# DL-1.net
KiCad netlist of a schematic drawn in EAGLE
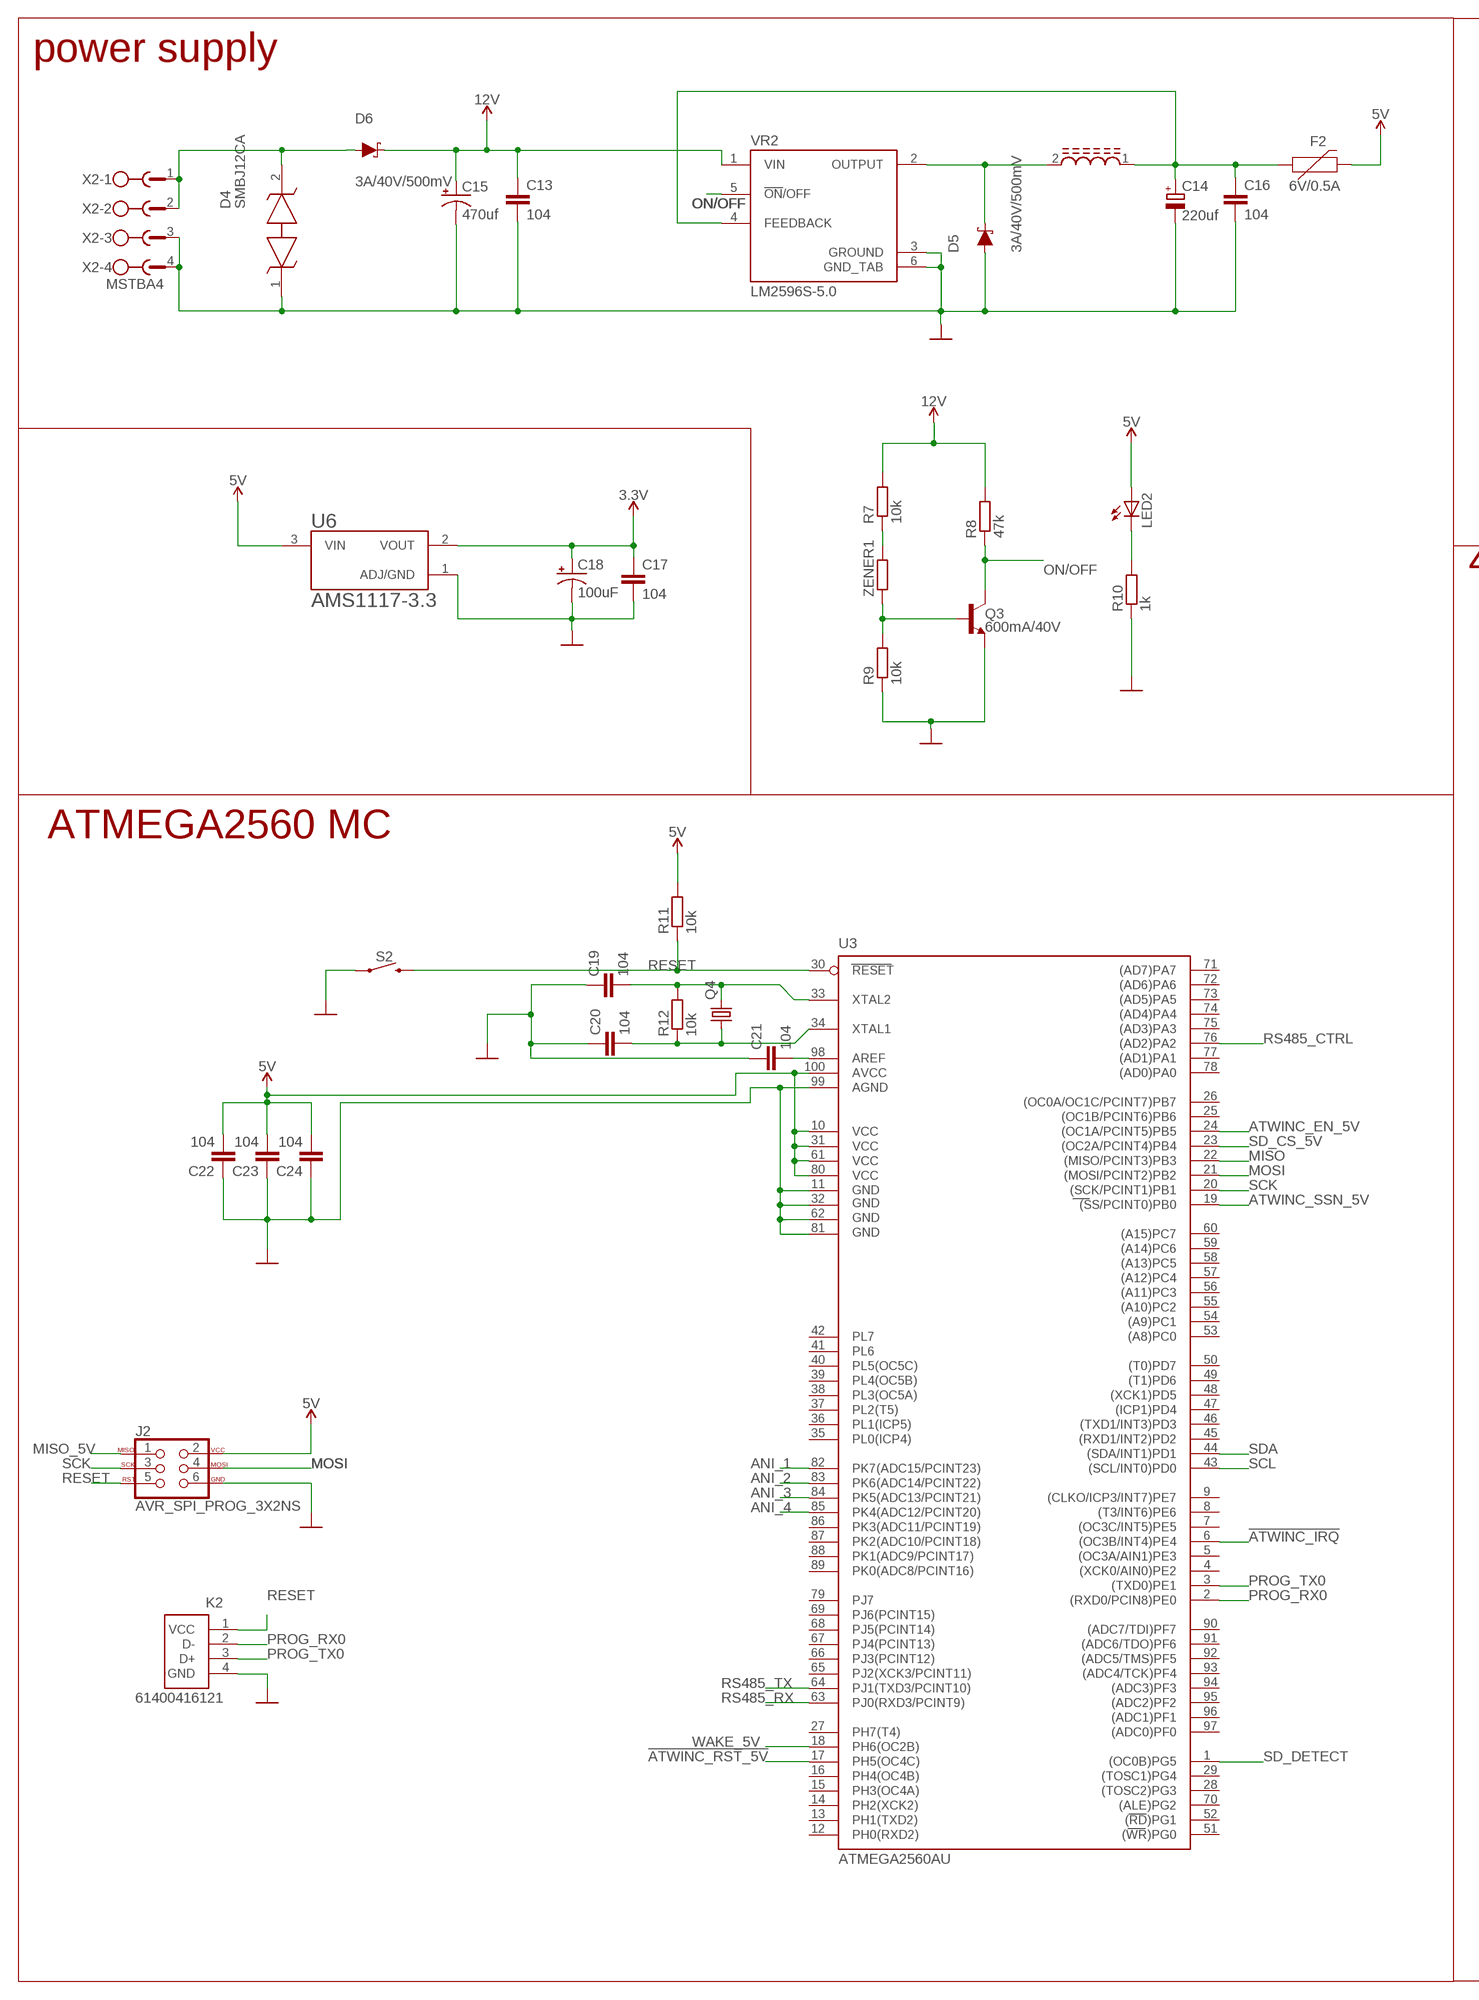
[diagram p0: schematic, sheet 1, part 1 of 2]
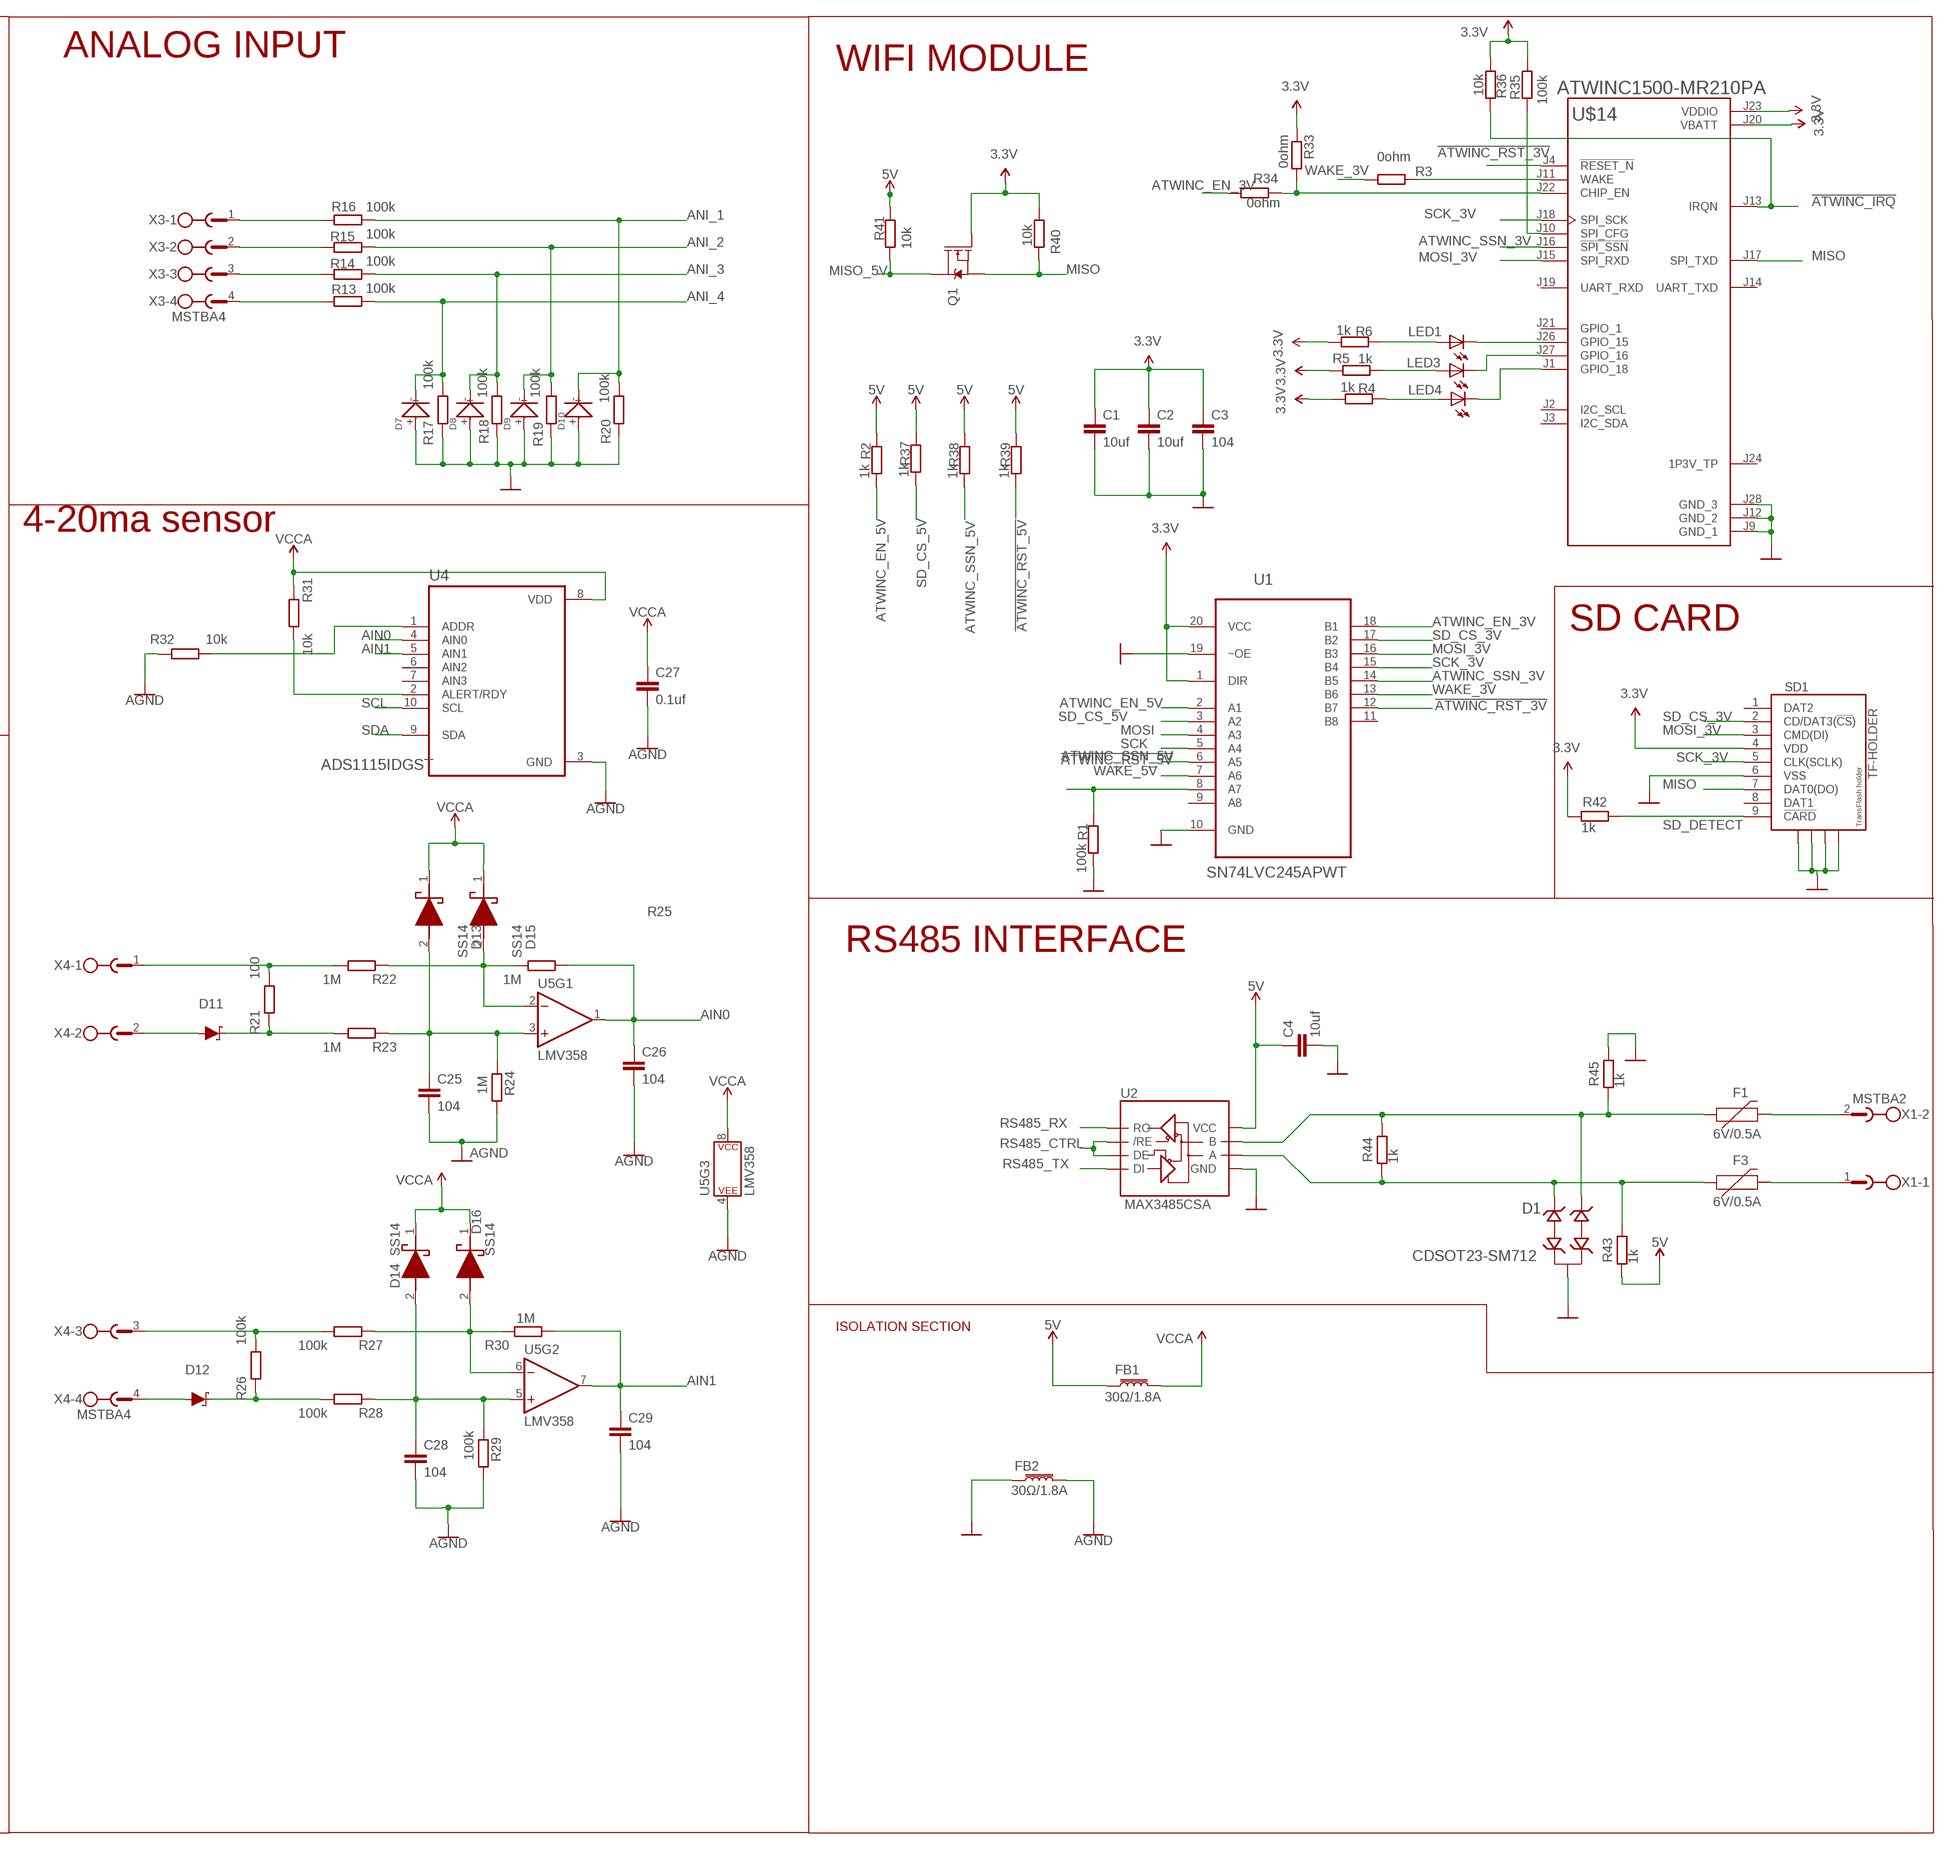
[diagram p1: schematic, sheet 1, part 2 of 2]

(export (version "E")
  (design (tool "Eeschema 10.0.6"))
  (components
    (comp (ref "C1")
      (value "10uf")
      (footprint "eagle-import:C0805")
      (libsource (lib "eagle-import") (part "C-EUC0805"))
    )
    (comp (ref "C2")
      (value "10uf")
      (footprint "eagle-import:C0805")
      (libsource (lib "eagle-import") (part "C-EUC0805"))
    )
    (comp (ref "C3")
      (value "104")
      (footprint "eagle-import:C0805")
      (libsource (lib "eagle-import") (part "C-EUC0805"))
    )
    (comp (ref "C4")
      (value "10uf")
      (footprint "eagle-import:C0805")
      (libsource (lib "eagle-import") (part "C-EUC0805"))
    )
    (comp (ref "C13")
      (value "104")
      (footprint "eagle-import:C0805")
      (libsource (lib "eagle-import") (part "C-EUC0805"))
    )
    (comp (ref "C14")
      (value "220uf")
      (footprint "eagle-import:153CLV-1014")
      (libsource (lib "eagle-import") (part "CPOL-EU153CLV-1014"))
    )
    (comp (ref "C15")
      (value "470uf")
      (footprint "eagle-import:E5-8,5")
      (libsource (lib "eagle-import") (part "CPOL-USE5-8.5"))
    )
    (comp (ref "C16")
      (value "104")
      (footprint "eagle-import:C0805")
      (libsource (lib "eagle-import") (part "C-EUC0805"))
    )
    (comp (ref "C17")
      (value "104")
      (footprint "eagle-import:C0805")
      (libsource (lib "eagle-import") (part "C-EUC0805"))
    )
    (comp (ref "C18")
      (value "100uF")
      (footprint "eagle-import:NIC_10X10.5_CAP")
      (libsource (lib "eagle-import") (part "100UF-POLAR-10X10.5-63V-20%"))
    )
    (comp (ref "C19")
      (value "104")
      (footprint "eagle-import:C0805")
      (libsource (lib "eagle-import") (part "C-EUC0805"))
    )
    (comp (ref "C20")
      (value "104")
      (footprint "eagle-import:C0805")
      (libsource (lib "eagle-import") (part "C-EUC0805"))
    )
    (comp (ref "C21")
      (value "104")
      (footprint "eagle-import:C0805")
      (libsource (lib "eagle-import") (part "C-EUC0805"))
    )
    (comp (ref "C22")
      (value "104")
      (footprint "eagle-import:C0805")
      (libsource (lib "eagle-import") (part "C-EUC0805"))
    )
    (comp (ref "C23")
      (value "104")
      (footprint "eagle-import:C0805")
      (libsource (lib "eagle-import") (part "C-EUC0805"))
    )
    (comp (ref "C24")
      (value "104")
      (footprint "eagle-import:C0805")
      (libsource (lib "eagle-import") (part "C-EUC0805"))
    )
    (comp (ref "C25")
      (value "104")
      (footprint "eagle-import:C0805")
      (libsource (lib "eagle-import") (part "C-EUC0805"))
    )
    (comp (ref "C26")
      (value "104")
      (footprint "eagle-import:C0805")
      (libsource (lib "eagle-import") (part "C-EUC0805"))
    )
    (comp (ref "C27")
      (value "0.1uf")
      (footprint "eagle-import:C0805")
      (libsource (lib "eagle-import") (part "C-EUC0805"))
    )
    (comp (ref "C28")
      (value "104")
      (footprint "eagle-import:C0805")
      (libsource (lib "eagle-import") (part "C-EUC0805"))
    )
    (comp (ref "C29")
      (value "104")
      (footprint "eagle-import:C0805")
      (libsource (lib "eagle-import") (part "C-EUC0805"))
    )
    (comp (ref "D1")
      (value "CDSOT23-SM712")
      (footprint "eagle-import:SOT-23-3")
      (fields (field (name "MF") "Bourns"))
      (libsource (lib "eagle-import") (part "CDSOT23-SM712"))
    )
    (comp (ref "D4")
      (value "SMBJ12CA")
      (footprint "eagle-import:DIONM5443X244N")
      (fields (field (name "MOUSER_PART_NUMBER") "652-SMBJ12CA"))
      (libsource (lib "eagle-import") (part "SMBJ12CA"))
    )
    (comp (ref "D5")
      (value "3A/40V/500mV")
      (footprint "eagle-import:SMA-DIODE")
      (libsource (lib "eagle-import") (part "DIODE-SCHOTTKY-B340A"))
    )
    (comp (ref "D6")
      (value "3A/40V/500mV")
      (footprint "eagle-import:SMA-DIODE")
      (libsource (lib "eagle-import") (part "DIODE-SCHOTTKY-B340A"))
    )
    (comp (ref "D7")
      (value "SMD-DIODE-ZENER-5.1V-500MW(SOD-123)")
      (footprint "eagle-import:SOD-123")
      (fields (field (name "MF") "Vishay") (field (name "MP") "MMSZ4689-V-GS08"))
      (libsource (lib "eagle-import") (part "SMD-DIODE-ZENER-5.1V-500MW(SOD-123)"))
    )
    (comp (ref "D8")
      (value "SMD-DIODE-ZENER-5.1V-500MW(SOD-123)")
      (footprint "eagle-import:SOD-123")
      (fields (field (name "MF") "Vishay") (field (name "MP") "MMSZ4689-V-GS08"))
      (libsource (lib "eagle-import") (part "SMD-DIODE-ZENER-5.1V-500MW(SOD-123)"))
    )
    (comp (ref "D9")
      (value "SMD-DIODE-ZENER-5.1V-500MW(SOD-123)")
      (footprint "eagle-import:SOD-123")
      (fields (field (name "MF") "Vishay") (field (name "MP") "MMSZ4689-V-GS08"))
      (libsource (lib "eagle-import") (part "SMD-DIODE-ZENER-5.1V-500MW(SOD-123)"))
    )
    (comp (ref "D10")
      (value "SMD-DIODE-ZENER-5.1V-500MW(SOD-123)")
      (footprint "eagle-import:SOD-123")
      (fields (field (name "MF") "Vishay") (field (name "MP") "MMSZ4689-V-GS08"))
      (libsource (lib "eagle-import") (part "SMD-DIODE-ZENER-5.1V-500MW(SOD-123)"))
    )
    (comp (ref "D11")
      (value "3A/40V/500mV")
      (footprint "eagle-import:SMA-DIODE")
      (libsource (lib "eagle-import") (part "DIODE-SCHOTTKY-B340A"))
    )
    (comp (ref "D12")
      (value "3A/40V/500mV")
      (footprint "eagle-import:SMA-DIODE")
      (libsource (lib "eagle-import") (part "DIODE-SCHOTTKY-B340A"))
    )
    (comp (ref "D13")
      (value "SS14")
      (footprint "eagle-import:DIOM5227X270N")
      (fields (field (name "MOUSER_PART_NUMBER") "512-SS14"))
      (libsource (lib "eagle-import") (part "SS14"))
    )
    (comp (ref "D14")
      (value "SS14")
      (footprint "eagle-import:DIOM5227X270N")
      (fields (field (name "MOUSER_PART_NUMBER") "512-SS14"))
      (libsource (lib "eagle-import") (part "SS14"))
    )
    (comp (ref "D15")
      (value "SS14")
      (footprint "eagle-import:DIOM5227X270N")
      (fields (field (name "MOUSER_PART_NUMBER") "512-SS14"))
      (libsource (lib "eagle-import") (part "SS14"))
    )
    (comp (ref "D16")
      (value "SS14")
      (footprint "eagle-import:DIOM5227X270N")
      (fields (field (name "MOUSER_PART_NUMBER") "512-SS14"))
      (libsource (lib "eagle-import") (part "SS14"))
    )
    (comp (ref "F1")
      (value "6V/0.5A")
      (footprint "eagle-import:1206")
      (libsource (lib "eagle-import") (part "PPTC_HALF-AMP"))
    )
    (comp (ref "F2")
      (value "6V/0.5A")
      (footprint "eagle-import:1206")
      (libsource (lib "eagle-import") (part "PPTC_HALF-AMP"))
    )
    (comp (ref "F3")
      (value "6V/0.5A")
      (footprint "eagle-import:1206")
      (libsource (lib "eagle-import") (part "PPTC_HALF-AMP"))
    )
    (comp (ref "FB1")
      (value "30Ω/1.8A")
      (footprint "eagle-import:0603")
      (libsource (lib "eagle-import") (part "FERRITE_BEAD-0603"))
    )
    (comp (ref "FB2")
      (value "30Ω/1.8A")
      (footprint "eagle-import:0603")
      (libsource (lib "eagle-import") (part "FERRITE_BEAD-0603"))
    )
    (comp (ref "J2")
      (value "AVR_SPI_PROG_3X2NS")
      (footprint "eagle-import:2X3-NS")
      (libsource (lib "eagle-import") (part "AVR_SPI_PROG_3X2NS"))
    )
    (comp (ref "K2")
      (value "61400416121")
      (footprint "eagle-import:61400416121")
      (libsource (lib "eagle-import") (part "61400416121"))
    )
    (comp (ref "L2")
      (value "SRR1260-680M")
      (footprint "eagle-import:INDP125125X600N")
      (fields (field (name "MF") "Bourns"))
      (libsource (lib "eagle-import") (part "SRR1260-680M"))
    )
    (comp (ref "LED1")
      (value "LEDCHIP-LED0805")
      (footprint "eagle-import:CHIP-LED0805")
      (libsource (lib "eagle-import") (part "LEDCHIP-LED0805"))
    )
    (comp (ref "LED2")
      (value "LEDCHIP-LED0805")
      (footprint "eagle-import:CHIP-LED0805")
      (libsource (lib "eagle-import") (part "LEDCHIP-LED0805"))
    )
    (comp (ref "LED3")
      (value "LEDCHIP-LED0805")
      (footprint "eagle-import:CHIP-LED0805")
      (libsource (lib "eagle-import") (part "LEDCHIP-LED0805"))
    )
    (comp (ref "LED4")
      (value "LEDCHIP-LED0805")
      (footprint "eagle-import:CHIP-LED0805")
      (libsource (lib "eagle-import") (part "LEDCHIP-LED0805"))
    )
    (comp (ref "Q1")
      (value "220mA/50V/3.5Ω")
      (footprint "eagle-import:SOT23-3")
      (libsource (lib "eagle-import") (part "MOSFET-NCH-BSS138"))
    )
    (comp (ref "Q3")
      (value "600mA/40V")
      (footprint "eagle-import:SOT23-3")
      (libsource (lib "eagle-import") (part "TRANS_NPN-MMBT2222AL"))
    )
    (comp (ref "Q4")
      (value "CRYSTALHC49S")
      (footprint "eagle-import:HC49_S")
      (libsource (lib "eagle-import") (part "CRYSTALHC49S"))
    )
    (comp (ref "R1")
      (value "100k")
      (footprint "eagle-import:M0805")
      (libsource (lib "eagle-import") (part "R-EU_M0805"))
    )
    (comp (ref "R2")
      (value "1k")
      (footprint "eagle-import:M0805")
      (libsource (lib "eagle-import") (part "R-EU_M0805"))
    )
    (comp (ref "R3")
      (value "0ohm")
      (footprint "eagle-import:M0805")
      (libsource (lib "eagle-import") (part "R-EU_M0805"))
    )
    (comp (ref "R4")
      (value "1k")
      (footprint "eagle-import:M0805")
      (libsource (lib "eagle-import") (part "R-EU_M0805"))
    )
    (comp (ref "R5")
      (value "1k")
      (footprint "eagle-import:M0805")
      (libsource (lib "eagle-import") (part "R-EU_M0805"))
    )
    (comp (ref "R6")
      (value "1k")
      (footprint "eagle-import:M0805")
      (libsource (lib "eagle-import") (part "R-EU_M0805"))
    )
    (comp (ref "R7")
      (value "10k")
      (footprint "eagle-import:M0805")
      (libsource (lib "eagle-import") (part "R-EU_M0805"))
    )
    (comp (ref "R8")
      (value "47k")
      (footprint "eagle-import:M0805")
      (libsource (lib "eagle-import") (part "R-EU_M0805"))
    )
    (comp (ref "R9")
      (value "10k")
      (footprint "eagle-import:M0805")
      (libsource (lib "eagle-import") (part "R-EU_M0805"))
    )
    (comp (ref "R10")
      (value "1k")
      (footprint "eagle-import:M0805")
      (libsource (lib "eagle-import") (part "R-EU_M0805"))
    )
    (comp (ref "R11")
      (value "10k")
      (footprint "eagle-import:M0805")
      (libsource (lib "eagle-import") (part "R-EU_M0805"))
    )
    (comp (ref "R12")
      (value "10k")
      (footprint "eagle-import:M0805")
      (libsource (lib "eagle-import") (part "R-EU_M0805"))
    )
    (comp (ref "R13")
      (value "100k")
      (footprint "eagle-import:M0805")
      (libsource (lib "eagle-import") (part "R-EU_M0805"))
    )
    (comp (ref "R14")
      (value "100k")
      (footprint "eagle-import:M0805")
      (libsource (lib "eagle-import") (part "R-EU_M0805"))
    )
    (comp (ref "R15")
      (value "100k")
      (footprint "eagle-import:M0805")
      (libsource (lib "eagle-import") (part "R-EU_M0805"))
    )
    (comp (ref "R16")
      (value "100k")
      (footprint "eagle-import:M0805")
      (libsource (lib "eagle-import") (part "R-EU_M0805"))
    )
    (comp (ref "R17")
      (value "100k")
      (footprint "eagle-import:M0805")
      (libsource (lib "eagle-import") (part "R-EU_M0805"))
    )
    (comp (ref "R18")
      (value "100k")
      (footprint "eagle-import:M0805")
      (libsource (lib "eagle-import") (part "R-EU_M0805"))
    )
    (comp (ref "R19")
      (value "100k")
      (footprint "eagle-import:M0805")
      (libsource (lib "eagle-import") (part "R-EU_M0805"))
    )
    (comp (ref "R20")
      (value "100k")
      (footprint "eagle-import:M0805")
      (libsource (lib "eagle-import") (part "R-EU_M0805"))
    )
    (comp (ref "R21")
      (value "100")
      (footprint "eagle-import:M0805")
      (libsource (lib "eagle-import") (part "R-EU_M0805"))
    )
    (comp (ref "R22")
      (value "1M")
      (footprint "eagle-import:M0805")
      (libsource (lib "eagle-import") (part "R-EU_M0805"))
    )
    (comp (ref "R23")
      (value "1M")
      (footprint "eagle-import:M0805")
      (libsource (lib "eagle-import") (part "R-EU_M0805"))
    )
    (comp (ref "R24")
      (value "1M")
      (footprint "eagle-import:M0805")
      (libsource (lib "eagle-import") (part "R-EU_M0805"))
    )
    (comp (ref "R25")
      (value "1M")
      (footprint "eagle-import:M0805")
      (libsource (lib "eagle-import") (part "R-EU_M0805"))
    )
    (comp (ref "R26")
      (value "100k")
      (footprint "eagle-import:M0805")
      (libsource (lib "eagle-import") (part "R-EU_M0805"))
    )
    (comp (ref "R27")
      (value "100k")
      (footprint "eagle-import:M0805")
      (libsource (lib "eagle-import") (part "R-EU_M0805"))
    )
    (comp (ref "R28")
      (value "100k")
      (footprint "eagle-import:M0805")
      (libsource (lib "eagle-import") (part "R-EU_M0805"))
    )
    (comp (ref "R29")
      (value "100k")
      (footprint "eagle-import:M0805")
      (libsource (lib "eagle-import") (part "R-EU_M0805"))
    )
    (comp (ref "R30")
      (value "1M")
      (footprint "eagle-import:M0805")
      (libsource (lib "eagle-import") (part "R-EU_M0805"))
    )
    (comp (ref "R31")
      (value "10k")
      (footprint "eagle-import:M0805")
      (libsource (lib "eagle-import") (part "R-EU_M0805"))
    )
    (comp (ref "R32")
      (value "10k")
      (footprint "eagle-import:M0805")
      (libsource (lib "eagle-import") (part "R-EU_M0805"))
    )
    (comp (ref "R33")
      (value "0ohm")
      (footprint "eagle-import:M0805")
      (libsource (lib "eagle-import") (part "R-EU_M0805"))
    )
    (comp (ref "R34")
      (value "0ohm")
      (footprint "eagle-import:M0805")
      (libsource (lib "eagle-import") (part "R-EU_M0805"))
    )
    (comp (ref "R35")
      (value "100k")
      (footprint "eagle-import:M0805")
      (libsource (lib "eagle-import") (part "R-EU_M0805"))
    )
    (comp (ref "R36")
      (value "10k")
      (footprint "eagle-import:M0805")
      (libsource (lib "eagle-import") (part "R-EU_M0805"))
    )
    (comp (ref "R37")
      (value "1k")
      (footprint "eagle-import:M0805")
      (libsource (lib "eagle-import") (part "R-EU_M0805"))
    )
    (comp (ref "R38")
      (value "1k")
      (footprint "eagle-import:M0805")
      (libsource (lib "eagle-import") (part "R-EU_M0805"))
    )
    (comp (ref "R39")
      (value "1k")
      (footprint "eagle-import:M0805")
      (libsource (lib "eagle-import") (part "R-EU_M0805"))
    )
    (comp (ref "R40")
      (value "10k")
      (footprint "eagle-import:M0805")
      (libsource (lib "eagle-import") (part "R-EU_M0805"))
    )
    (comp (ref "R41")
      (value "10k")
      (footprint "eagle-import:M0805")
      (libsource (lib "eagle-import") (part "R-EU_M0805"))
    )
    (comp (ref "R42")
      (value "1k")
      (footprint "eagle-import:M0805")
      (libsource (lib "eagle-import") (part "R-EU_M0805"))
    )
    (comp (ref "R43")
      (value "1k")
      (footprint "eagle-import:M0805")
      (libsource (lib "eagle-import") (part "R-EU_M0805"))
    )
    (comp (ref "R44")
      (value "1k")
      (footprint "eagle-import:M0805")
      (libsource (lib "eagle-import") (part "R-EU_M0805"))
    )
    (comp (ref "R45")
      (value "1k")
      (footprint "eagle-import:M0805")
      (libsource (lib "eagle-import") (part "R-EU_M0805"))
    )
    (comp (ref "S2")
      (value "MOMENTARY-SWITCH-SPST-SMD-6.0X3.5MM")
      (footprint "eagle-import:TACTILE_SWITCH_SMD_6.0X3.5MM")
      (libsource (lib "eagle-import") (part "MOMENTARY-SWITCH-SPST-SMD-6.0X3.5MM"))
    )
    (comp (ref "SD1")
      (value "TF-HOLDER")
      (footprint "eagle-import:TF-PULL")
      (libsource (lib "eagle-import") (part "TF-HOLDER"))
    )
    (comp (ref "U$14")
      (value "ATWINC1500-MR210PA")
      (footprint "eagle-import:ATMEL_ATWINC1500-MR210PA")
      (fields (field (name "MF") "Microchip"))
      (libsource (lib "eagle-import") (part "ATWINC1500-MR210PA"))
    )
    (comp (ref "U1")
      (value "SN74LVC245APWT")
      (footprint "eagle-import:SOP65P640X120-20N")
      (fields (field (name "MF") "Texas Instruments"))
      (libsource (lib "eagle-import") (part "SN74LVC245APWT"))
    )
    (comp (ref "U2")
      (value "MAX3485CSA")
      (footprint "eagle-import:SO08")
      (libsource (lib "eagle-import") (part "RS485SOIC"))
    )
    (comp (ref "U3")
      (value "ATMEGA2560AU")
      (footprint "eagle-import:TQFP100")
      (libsource (lib "eagle-import") (part "ATMEGA2560AU"))
    )
    (comp (ref "U4")
      (value "ADS1115IDGST")
      (footprint "eagle-import:SOP50P490X110-10N")
      (fields (field (name "MF") "Texas Instruments"))
      (libsource (lib "eagle-import") (part "ADS1115IDGST"))
    )
    (comp (ref "U5")
      (value "LMV358")
      (footprint "eagle-import:SO08")
      (libsource (lib "eagle-import") (part "LMV358SOIC"))
    )
    (comp (ref "U6")
      (value "AMS1117-3.3")
      (footprint "eagle-import:SOT229P700X180-4N")
      (fields (field (name "MF") "Advanced Monolithic Systems"))
      (libsource (lib "eagle-import") (part "AMS1117-3.3"))
    )
    (comp (ref "VR2")
      (value "LM2596S-5.0")
      (footprint "eagle-import:TO170P1524X483-6N")
      (fields (field (name "MF") "Texas"))
      (libsource (lib "eagle-import") (part "LM2596S-5.0"))
    )
    (comp (ref "X1")
      (value "MSTBA2")
      (footprint "eagle-import:MSTBA2")
      (fields (field (name "MF") "FARNELL") (field (name "MPN") "1757242"))
      (libsource (lib "eagle-import") (part "MSTBA2"))
    )
    (comp (ref "X2")
      (value "MSTBA4")
      (footprint "eagle-import:MSTBA4")
      (fields (field (name "MF") "FARNELL") (field (name "MPN") "1757268"))
      (libsource (lib "eagle-import") (part "MSTBA4"))
    )
    (comp (ref "X3")
      (value "MSTBA4")
      (footprint "eagle-import:MSTBA4")
      (fields (field (name "MF") "FARNELL") (field (name "MPN") "1757268"))
      (libsource (lib "eagle-import") (part "MSTBA4"))
    )
    (comp (ref "X4")
      (value "MSTBA4")
      (footprint "eagle-import:MSTBA4")
      (fields (field (name "MF") "FARNELL") (field (name "MPN") "1757268"))
      (libsource (lib "eagle-import") (part "MSTBA4"))
    )
    (comp (ref "ZENER1")
      (value "R-EU_0204/7")
      (footprint "eagle-import:0204_7")
      (libsource (lib "eagle-import") (part "R-EU_0204/7"))
    )
  )
  (nets
    (net (code "1") (name "/AIN0") (class "Default")
      (node (ref "C26") (pin "1") (pinfunction "1_1") (pintype "passive"))
      (node (ref "R25") (pin "1") (pinfunction "1_1") (pintype "passive"))
      (node (ref "U4") (pin "4") (pinfunction "AIN0_4") (pintype "input"))
      (node (ref "U5") (pin "1") (pinfunction "OUT_1") (pintype "output"))
    )
    (net (code "2") (name "/AIN1") (class "Default")
      (node (ref "C29") (pin "1") (pinfunction "1_1") (pintype "passive"))
      (node (ref "R30") (pin "1") (pinfunction "1_1") (pintype "passive"))
      (node (ref "U4") (pin "5") (pinfunction "AIN1_5") (pintype "input"))
      (node (ref "U5") (pin "7") (pinfunction "OUT_7") (pintype "output"))
    )
    (net (code "3") (name "/ANI_1") (class "Default")
      (node (ref "D10") (pin "-") (pinfunction "-_-") (pintype "passive"))
      (node (ref "R16") (pin "1") (pinfunction "1_1") (pintype "passive"))
      (node (ref "R20") (pin "2") (pinfunction "2_2") (pintype "passive"))
      (node (ref "U3") (pin "82") (pinfunction "PK7(ADC15/PCINT23)_82") (pintype "bidirectional"))
    )
    (net (code "4") (name "/ANI_2") (class "Default")
      (node (ref "D9") (pin "-") (pinfunction "-_-") (pintype "passive"))
      (node (ref "R15") (pin "1") (pinfunction "1_1") (pintype "passive"))
      (node (ref "R19") (pin "2") (pinfunction "2_2") (pintype "passive"))
      (node (ref "U3") (pin "83") (pinfunction "PK6(ADC14/PCINT22)_83") (pintype "bidirectional"))
    )
    (net (code "5") (name "/ANI_3") (class "Default")
      (node (ref "D8") (pin "-") (pinfunction "-_-") (pintype "passive"))
      (node (ref "R14") (pin "1") (pinfunction "1_1") (pintype "passive"))
      (node (ref "R18") (pin "2") (pinfunction "2_2") (pintype "passive"))
      (node (ref "U3") (pin "84") (pinfunction "PK5(ADC13/PCINT21)_84") (pintype "bidirectional"))
    )
    (net (code "6") (name "/ANI_4") (class "Default")
      (node (ref "D7") (pin "-") (pinfunction "-_-") (pintype "passive"))
      (node (ref "R13") (pin "1") (pinfunction "1_1") (pintype "passive"))
      (node (ref "R17") (pin "2") (pinfunction "2_2") (pintype "passive"))
      (node (ref "U3") (pin "85") (pinfunction "PK4(ADC12/PCINT20)_85") (pintype "bidirectional"))
    )
    (net (code "7") (name "/ATWINC_EN_3V") (class "Default")
      (node (ref "R34") (pin "1") (pinfunction "1_1") (pintype "passive"))
      (node (ref "U1") (pin "18") (pinfunction "B1_18") (pintype "bidirectional"))
    )
    (net (code "8") (name "/ATWINC_EN_5V") (class "Default")
      (node (ref "R2") (pin "2") (pinfunction "2_2") (pintype "passive"))
      (node (ref "U1") (pin "2") (pinfunction "A1_2") (pintype "bidirectional"))
      (node (ref "U3") (pin "24") (pinfunction "(OC1A/PCINT5)PB5_24") (pintype "bidirectional"))
    )
    (net (code "9") (name "/ATWINC_SSN_3V") (class "Default")
      (node (ref "U$14") (pin "J16") (pinfunction "~{SPI_SSN}_J16") (pintype "input"))
      (node (ref "U1") (pin "14") (pinfunction "B5_14") (pintype "bidirectional"))
    )
    (net (code "10") (name "/ATWINC_SSN_5V") (class "Default")
      (node (ref "R38") (pin "2") (pinfunction "2_2") (pintype "passive"))
      (node (ref "U1") (pin "6") (pinfunction "A5_6") (pintype "bidirectional"))
      (node (ref "U3") (pin "19") (pinfunction "(SS/PCINT0)PB0_19") (pintype "bidirectional"))
    )
    (net (code "11") (name "/MISO") (class "Default")
      (node (ref "Q1") (pin "2") (pinfunction "S_2") (pintype "bidirectional"))
      (node (ref "R40") (pin "2") (pinfunction "2_2") (pintype "passive"))
      (node (ref "SD1") (pin "7") (pinfunction "DAT0(DO)_7") (pintype "bidirectional"))
      (node (ref "U$14") (pin "J17") (pinfunction "SPI_TXD_J17") (pintype "output"))
      (node (ref "U3") (pin "22") (pinfunction "(MISO/PCINT3)PB3_22") (pintype "bidirectional"))
    )
    (net (code "12") (name "/MISO_5V") (class "Default")
      (node (ref "J2") (pin "1") (pinfunction "1_1") (pintype "passive"))
      (node (ref "Q1") (pin "3") (pinfunction "D_3") (pintype "bidirectional"))
      (node (ref "R41") (pin "2") (pinfunction "2_2") (pintype "passive"))
    )
    (net (code "13") (name "/MOSI") (class "Default")
      (node (ref "J2") (pin "4") (pinfunction "4_4") (pintype "passive"))
      (node (ref "U1") (pin "4") (pinfunction "A3_4") (pintype "bidirectional"))
      (node (ref "U3") (pin "21") (pinfunction "(MOSI/PCINT2)PB2_21") (pintype "bidirectional"))
    )
    (net (code "14") (name "/MOSI_3V") (class "Default")
      (node (ref "SD1") (pin "3") (pinfunction "CMD(DI)_3") (pintype "bidirectional"))
      (node (ref "U$14") (pin "J15") (pinfunction "SPI_RXD_J15") (pintype "input"))
      (node (ref "U1") (pin "16") (pinfunction "B3_16") (pintype "bidirectional"))
    )
    (net (code "15") (name "/ON{slash}OFF") (class "Default")
      (node (ref "Q3") (pin "3") (pinfunction "C_3") (pintype "passive"))
      (node (ref "R8") (pin "1") (pinfunction "1_1") (pintype "passive"))
      (node (ref "VR2") (pin "5") (pinfunction "~{ON}/OFF_5") (pintype "input"))
    )
    (net (code "16") (name "/PROG_RX0") (class "Default")
      (node (ref "K2") (pin "2") (pinfunction "D-_2") (pintype "passive"))
      (node (ref "U3") (pin "2") (pinfunction "(RXD0/PCIN8)PE0_2") (pintype "bidirectional"))
    )
    (net (code "17") (name "/PROG_TX0") (class "Default")
      (node (ref "K2") (pin "3") (pinfunction "D+_3") (pintype "passive"))
      (node (ref "U3") (pin "3") (pinfunction "(TXD0)PE1_3") (pintype "bidirectional"))
    )
    (net (code "18") (name "/RESET") (class "Default")
      (node (ref "J2") (pin "5") (pinfunction "5_5") (pintype "passive"))
      (node (ref "K2") (pin "1") (pinfunction "VCC_1") (pintype "passive"))
      (node (ref "R11") (pin "1") (pinfunction "1_1") (pintype "passive"))
      (node (ref "S2") (pin "2") (pinfunction "2_2") (pintype "passive"))
      (node (ref "U3") (pin "30") (pinfunction "RESET_30") (pintype "input"))
    )
    (net (code "19") (name "/RS485_CTRL") (class "Default")
      (node (ref "U2") (pin "2") (pinfunction "/RE_2") (pintype "bidirectional"))
      (node (ref "U2") (pin "3") (pinfunction "DE_3") (pintype "bidirectional"))
      (node (ref "U3") (pin "76") (pinfunction "(AD2)PA2_76") (pintype "bidirectional"))
    )
    (net (code "20") (name "/RS485_RX") (class "Default")
      (node (ref "U2") (pin "1") (pinfunction "RO_1") (pintype "bidirectional"))
      (node (ref "U3") (pin "63") (pinfunction "PJ0(RXD3/PCINT9)_63") (pintype "bidirectional"))
    )
    (net (code "21") (name "/RS485_TX") (class "Default")
      (node (ref "U2") (pin "4") (pinfunction "DI_4") (pintype "bidirectional"))
      (node (ref "U3") (pin "64") (pinfunction "PJ1(TXD3/PCINT10)_64") (pintype "bidirectional"))
    )
    (net (code "22") (name "/SCK") (class "Default")
      (node (ref "J2") (pin "3") (pinfunction "3_3") (pintype "passive"))
      (node (ref "U1") (pin "5") (pinfunction "A4_5") (pintype "bidirectional"))
      (node (ref "U3") (pin "20") (pinfunction "(SCK/PCINT1)PB1_20") (pintype "bidirectional"))
    )
    (net (code "23") (name "/SCK_3V") (class "Default")
      (node (ref "SD1") (pin "5") (pinfunction "CLK(SCLK)_5") (pintype "input"))
      (node (ref "U$14") (pin "J18") (pinfunction "SPI_SCK_J18") (pintype "input"))
      (node (ref "U1") (pin "15") (pinfunction "B4_15") (pintype "bidirectional"))
    )
    (net (code "24") (name "/SCL") (class "Default")
      (node (ref "U3") (pin "43") (pinfunction "(SCL/INT0)PD0_43") (pintype "bidirectional"))
      (node (ref "U4") (pin "10") (pinfunction "SCL_10") (pintype "input"))
    )
    (net (code "25") (name "/SDA") (class "Default")
      (node (ref "U3") (pin "44") (pinfunction "(SDA/INT1)PD1_44") (pintype "bidirectional"))
      (node (ref "U4") (pin "9") (pinfunction "SDA_9") (pintype "bidirectional"))
    )
    (net (code "26") (name "/SD_CS_3V") (class "Default")
      (node (ref "SD1") (pin "2") (pinfunction "CD/DAT3(~{CS})_2") (pintype "bidirectional"))
      (node (ref "U1") (pin "17") (pinfunction "B2_17") (pintype "bidirectional"))
    )
    (net (code "27") (name "/SD_CS_5V") (class "Default")
      (node (ref "R37") (pin "2") (pinfunction "2_2") (pintype "passive"))
      (node (ref "U1") (pin "3") (pinfunction "A2_3") (pintype "bidirectional"))
      (node (ref "U3") (pin "23") (pinfunction "(OC2A/PCINT4)PB4_23") (pintype "bidirectional"))
    )
    (net (code "28") (name "/SD_DETECT") (class "Default")
      (node (ref "R42") (pin "2") (pinfunction "2_2") (pintype "passive"))
      (node (ref "SD1") (pin "9") (pinfunction "~{CARD}_9") (pintype "passive"))
      (node (ref "U3") (pin "1") (pinfunction "(OC0B)PG5_1") (pintype "bidirectional"))
    )
    (net (code "29") (name "/WAKE_3V") (class "Default")
      (node (ref "R3") (pin "2") (pinfunction "2_2") (pintype "passive"))
      (node (ref "U1") (pin "13") (pinfunction "B6_13") (pintype "bidirectional"))
    )
    (net (code "30") (name "/WAKE_5V") (class "Default")
      (node (ref "U1") (pin "7") (pinfunction "A6_7") (pintype "bidirectional"))
      (node (ref "U3") (pin "18") (pinfunction "PH6(OC2B)_18") (pintype "bidirectional"))
    )
    (net (code "31") (name "/~{ATWINC_IRQ}") (class "Default")
      (node (ref "R36") (pin "2") (pinfunction "2_2") (pintype "passive"))
      (node (ref "U$14") (pin "J13") (pinfunction "IRQN_J13") (pintype "output"))
      (node (ref "U3") (pin "6") (pinfunction "(OC3B/INT4)PE4_6") (pintype "bidirectional"))
    )
    (net (code "32") (name "/~{ATWINC_RST_3V}") (class "Default")
      (node (ref "U$14") (pin "J4") (pinfunction "~{RESET_N}_J4") (pintype "input"))
      (node (ref "U1") (pin "12") (pinfunction "B7_12") (pintype "bidirectional"))
    )
    (net (code "33") (name "/~{ATWINC_RST_5V}") (class "Default")
      (node (ref "R1") (pin "1") (pinfunction "1_1") (pintype "passive"))
      (node (ref "R39") (pin "2") (pinfunction "2_2") (pintype "passive"))
      (node (ref "U1") (pin "8") (pinfunction "A7_8") (pintype "bidirectional"))
      (node (ref "U3") (pin "17") (pinfunction "PH5(OC4C)_17") (pintype "bidirectional"))
    )
    (net (code "34") (name "3.3V") (class "Default")
      (node (ref "C1") (pin "1") (pinfunction "1_1") (pintype "passive"))
      (node (ref "C17") (pin "1") (pinfunction "1_1") (pintype "passive"))
      (node (ref "C18") (pin "+") (pinfunction "+_+") (pintype "passive"))
      (node (ref "C2") (pin "1") (pinfunction "1_1") (pintype "passive"))
      (node (ref "C3") (pin "1") (pinfunction "1_1") (pintype "passive"))
      (node (ref "Q1") (pin "1") (pinfunction "G_1") (pintype "bidirectional"))
      (node (ref "R33") (pin "1") (pinfunction "1_1") (pintype "passive"))
      (node (ref "R35") (pin "1") (pinfunction "1_1") (pintype "passive"))
      (node (ref "R36") (pin "1") (pinfunction "1_1") (pintype "passive"))
      (node (ref "R4") (pin "2") (pinfunction "2_2") (pintype "passive"))
      (node (ref "R40") (pin "1") (pinfunction "1_1") (pintype "passive"))
      (node (ref "R42") (pin "1") (pinfunction "1_1") (pintype "passive"))
      (node (ref "R5") (pin "2") (pinfunction "2_2") (pintype "passive"))
      (node (ref "R6") (pin "2") (pinfunction "2_2") (pintype "passive"))
      (node (ref "SD1") (pin "4") (pinfunction "VDD_4") (pintype "power_in"))
      (node (ref "U$14") (pin "J20") (pinfunction "VBATT_J20") (pintype "power_in"))
      (node (ref "U$14") (pin "J23") (pinfunction "VDDIO_J23") (pintype "power_in"))
      (node (ref "U1") (pin "1") (pinfunction "DIR_1") (pintype "input"))
      (node (ref "U1") (pin "20") (pinfunction "VCC_20") (pintype "power_in"))
      (node (ref "U6") (pin "2") (pinfunction "VOUT_2") (pintype "output"))
    )
    (net (code "35") (name "5V") (class "Default")
      (node (ref "C22") (pin "2") (pinfunction "2_2") (pintype "passive"))
      (node (ref "C23") (pin "2") (pinfunction "2_2") (pintype "passive"))
      (node (ref "C24") (pin "2") (pinfunction "2_2") (pintype "passive"))
      (node (ref "C4") (pin "1") (pinfunction "1_1") (pintype "passive"))
      (node (ref "F2") (pin "2") (pinfunction "2_2") (pintype "bidirectional"))
      (node (ref "FB1") (pin "1") (pinfunction "1_1") (pintype "passive"))
      (node (ref "J2") (pin "2") (pinfunction "2_2") (pintype "passive"))
      (node (ref "LED2") (pin "A") (pinfunction "A_A") (pintype "passive"))
      (node (ref "R11") (pin "2") (pinfunction "2_2") (pintype "passive"))
      (node (ref "R2") (pin "1") (pinfunction "1_1") (pintype "passive"))
      (node (ref "R37") (pin "1") (pinfunction "1_1") (pintype "passive"))
      (node (ref "R38") (pin "1") (pinfunction "1_1") (pintype "passive"))
      (node (ref "R39") (pin "1") (pinfunction "1_1") (pintype "passive"))
      (node (ref "R41") (pin "1") (pinfunction "1_1") (pintype "passive"))
      (node (ref "R43") (pin "1") (pinfunction "1_1") (pintype "passive"))
      (node (ref "U2") (pin "8") (pinfunction "VCC_8") (pintype "bidirectional"))
      (node (ref "U3") (pin "10") (pinfunction "VCC_10") (pintype "power_in"))
      (node (ref "U3") (pin "100") (pinfunction "AVCC_100") (pintype "power_in"))
      (node (ref "U3") (pin "31") (pinfunction "VCC1_31") (pintype "power_in"))
      (node (ref "U3") (pin "61") (pinfunction "VCC2_61") (pintype "power_in"))
      (node (ref "U3") (pin "80") (pinfunction "VCC3_80") (pintype "power_in"))
      (node (ref "U6") (pin "3") (pinfunction "VIN_3") (pintype "input"))
    )
    (net (code "36") (name "12V") (class "Default")
      (node (ref "C13") (pin "1") (pinfunction "1_1") (pintype "passive"))
      (node (ref "C15") (pin "+") (pinfunction "+_+") (pintype "passive"))
      (node (ref "D6") (pin "C") (pinfunction "C_C") (pintype "passive"))
      (node (ref "R7") (pin "2") (pinfunction "2_2") (pintype "passive"))
      (node (ref "R8") (pin "2") (pinfunction "2_2") (pintype "passive"))
      (node (ref "VR2") (pin "1") (pinfunction "VIN_1") (pintype "input"))
    )
    (net (code "37") (name "AGND") (class "Default")
      (node (ref "C25") (pin "2") (pinfunction "2_2") (pintype "passive"))
      (node (ref "C26") (pin "2") (pinfunction "2_2") (pintype "passive"))
      (node (ref "C27") (pin "2") (pinfunction "2_2") (pintype "passive"))
      (node (ref "C28") (pin "2") (pinfunction "2_2") (pintype "passive"))
      (node (ref "C29") (pin "2") (pinfunction "2_2") (pintype "passive"))
      (node (ref "FB2") (pin "2") (pinfunction "2_2") (pintype "passive"))
      (node (ref "R24") (pin "1") (pinfunction "1_1") (pintype "passive"))
      (node (ref "R29") (pin "1") (pinfunction "1_1") (pintype "passive"))
      (node (ref "R32") (pin "1") (pinfunction "1_1") (pintype "passive"))
      (node (ref "U4") (pin "3") (pinfunction "GND_3") (pintype "power_in"))
      (node (ref "U5") (pin "4") (pinfunction "P$V-_4") (pintype "bidirectional"))
    )
    (net (code "38") (name "GND") (class "Default")
      (node (ref "C1") (pin "2") (pinfunction "2_2") (pintype "passive"))
      (node (ref "C13") (pin "2") (pinfunction "2_2") (pintype "passive"))
      (node (ref "C14") (pin "-") (pinfunction "-_-") (pintype "passive"))
      (node (ref "C15") (pin "-") (pinfunction "-_-") (pintype "passive"))
      (node (ref "C16") (pin "2") (pinfunction "2_2") (pintype "passive"))
      (node (ref "C17") (pin "2") (pinfunction "2_2") (pintype "passive"))
      (node (ref "C18") (pin "-") (pinfunction "-_-") (pintype "passive"))
      (node (ref "C19") (pin "1") (pinfunction "1_1") (pintype "passive"))
      (node (ref "C2") (pin "2") (pinfunction "2_2") (pintype "passive"))
      (node (ref "C20") (pin "1") (pinfunction "1_1") (pintype "passive"))
      (node (ref "C21") (pin "1") (pinfunction "1_1") (pintype "passive"))
      (node (ref "C22") (pin "1") (pinfunction "1_1") (pintype "passive"))
      (node (ref "C23") (pin "1") (pinfunction "1_1") (pintype "passive"))
      (node (ref "C24") (pin "1") (pinfunction "1_1") (pintype "passive"))
      (node (ref "C3") (pin "2") (pinfunction "2_2") (pintype "passive"))
      (node (ref "C4") (pin "2") (pinfunction "2_2") (pintype "passive"))
      (node (ref "D1") (pin "3") (pinfunction "GND_3") (pintype "bidirectional"))
      (node (ref "D10") (pin "+") (pinfunction "+_+") (pintype "passive"))
      (node (ref "D4") (pin "1") (pinfunction "1_1") (pintype "bidirectional"))
      (node (ref "D5") (pin "A") (pinfunction "A_A") (pintype "passive"))
      (node (ref "D7") (pin "+") (pinfunction "+_+") (pintype "passive"))
      (node (ref "D8") (pin "+") (pinfunction "+_+") (pintype "passive"))
      (node (ref "D9") (pin "+") (pinfunction "+_+") (pintype "passive"))
      (node (ref "FB2") (pin "1") (pinfunction "1_1") (pintype "passive"))
      (node (ref "J2") (pin "6") (pinfunction "6_6") (pintype "passive"))
      (node (ref "K2") (pin "4") (pinfunction "GND_4") (pintype "passive"))
      (node (ref "Q3") (pin "2") (pinfunction "E_2") (pintype "passive"))
      (node (ref "R1") (pin "2") (pinfunction "2_2") (pintype "passive"))
      (node (ref "R10") (pin "1") (pinfunction "1_1") (pintype "passive"))
      (node (ref "R17") (pin "1") (pinfunction "1_1") (pintype "passive"))
      (node (ref "R18") (pin "1") (pinfunction "1_1") (pintype "passive"))
      (node (ref "R19") (pin "1") (pinfunction "1_1") (pintype "passive"))
      (node (ref "R20") (pin "1") (pinfunction "1_1") (pintype "passive"))
      (node (ref "R45") (pin "2") (pinfunction "2_2") (pintype "passive"))
      (node (ref "R9") (pin "1") (pinfunction "1_1") (pintype "passive"))
      (node (ref "S2") (pin "1") (pinfunction "1_1") (pintype "passive"))
      (node (ref "SD1") (pin "6") (pinfunction "VSS_6") (pintype "power_in"))
      (node (ref "SD1") (pin "S1") (pinfunction "S1_S1") (pintype "passive"))
      (node (ref "SD1") (pin "S2") (pinfunction "S2_S2") (pintype "passive"))
      (node (ref "SD1") (pin "S3") (pinfunction "S3_S3") (pintype "passive"))
      (node (ref "SD1") (pin "S4") (pinfunction "S4_S4") (pintype "passive"))
      (node (ref "U$14") (pin "J12") (pinfunction "GND_2_J12") (pintype "passive"))
      (node (ref "U$14") (pin "J28") (pinfunction "GND_3_J28") (pintype "passive"))
      (node (ref "U$14") (pin "J9") (pinfunction "GND_1_J9") (pintype "passive"))
      (node (ref "U1") (pin "10") (pinfunction "GND_10") (pintype "passive"))
      (node (ref "U1") (pin "19") (pinfunction "~{OE}_19") (pintype "input"))
      (node (ref "U2") (pin "5") (pinfunction "GND_5") (pintype "bidirectional"))
      (node (ref "U3") (pin "11") (pinfunction "GND_11") (pintype "power_in"))
      (node (ref "U3") (pin "32") (pinfunction "GND1_32") (pintype "power_in"))
      (node (ref "U3") (pin "62") (pinfunction "GND2_62") (pintype "power_in"))
      (node (ref "U3") (pin "81") (pinfunction "GND3_81") (pintype "power_in"))
      (node (ref "U3") (pin "99") (pinfunction "AGND_99") (pintype "power_in"))
      (node (ref "U6") (pin "1") (pinfunction "ADJ/GND_1") (pintype "power_in"))
      (node (ref "VR2") (pin "3") (pinfunction "GROUND_3") (pintype "power_in"))
      (node (ref "VR2") (pin "6") (pinfunction "GND_TAB_6") (pintype "power_in"))
      (node (ref "X2") (pin "3") (pinfunction "1_3") (pintype "passive"))
      (node (ref "X2") (pin "4") (pinfunction "1_4") (pintype "passive"))
    )
    (net (code "39") (name "Net-(D1-IO1)") (class "Default")
      (node (ref "D1") (pin "1") (pinfunction "IO1_1") (pintype "bidirectional"))
      (node (ref "F3") (pin "1") (pinfunction "1_1") (pintype "bidirectional"))
      (node (ref "R43") (pin "2") (pinfunction "2_2") (pintype "passive"))
      (node (ref "R44") (pin "1") (pinfunction "1_1") (pintype "passive"))
      (node (ref "U2") (pin "6") (pinfunction "A_6") (pintype "bidirectional"))
    )
    (net (code "40") (name "Net-(D1-IO2)") (class "Default")
      (node (ref "D1") (pin "2") (pinfunction "IO2_2") (pintype "bidirectional"))
      (node (ref "F1") (pin "1") (pinfunction "1_1") (pintype "bidirectional"))
      (node (ref "R44") (pin "2") (pinfunction "2_2") (pintype "passive"))
      (node (ref "R45") (pin "1") (pinfunction "1_1") (pintype "passive"))
      (node (ref "U2") (pin "7") (pinfunction "B_7") (pintype "bidirectional"))
    )
    (net (code "41") (name "Net-(D11-PadC)") (class "Default")
      (node (ref "D11") (pin "C") (pinfunction "C_C") (pintype "passive"))
      (node (ref "R21") (pin "1") (pinfunction "1_1") (pintype "passive"))
      (node (ref "R23") (pin "2") (pinfunction "2_2") (pintype "passive"))
    )
    (net (code "42") (name "Net-(D12-PadC)") (class "Default")
      (node (ref "D12") (pin "C") (pinfunction "C_C") (pintype "passive"))
      (node (ref "R26") (pin "1") (pinfunction "1_1") (pintype "passive"))
      (node (ref "R28") (pin "2") (pinfunction "2_2") (pintype "passive"))
    )
    (net (code "43") (name "Net-(D13-A)") (class "Default")
      (node (ref "C25") (pin "1") (pinfunction "1_1") (pintype "passive"))
      (node (ref "D13") (pin "2") (pinfunction "A_2") (pintype "bidirectional"))
      (node (ref "R23") (pin "1") (pinfunction "1_1") (pintype "passive"))
      (node (ref "R24") (pin "2") (pinfunction "2_2") (pintype "passive"))
      (node (ref "U5") (pin "3") (pinfunction "+IN_3") (pintype "input"))
    )
    (net (code "44") (name "Net-(D14-A)") (class "Default")
      (node (ref "C28") (pin "1") (pinfunction "1_1") (pintype "passive"))
      (node (ref "D14") (pin "2") (pinfunction "A_2") (pintype "bidirectional"))
      (node (ref "R28") (pin "1") (pinfunction "1_1") (pintype "passive"))
      (node (ref "R29") (pin "2") (pinfunction "2_2") (pintype "passive"))
      (node (ref "U5") (pin "5") (pinfunction "+IN_5") (pintype "input"))
    )
    (net (code "45") (name "Net-(D15-A)") (class "Default")
      (node (ref "D15") (pin "2") (pinfunction "A_2") (pintype "bidirectional"))
      (node (ref "R22") (pin "1") (pinfunction "1_1") (pintype "passive"))
      (node (ref "R25") (pin "2") (pinfunction "2_2") (pintype "passive"))
      (node (ref "U5") (pin "2") (pinfunction "-IN_2") (pintype "input"))
    )
    (net (code "46") (name "Net-(D16-A)") (class "Default")
      (node (ref "D16") (pin "2") (pinfunction "A_2") (pintype "bidirectional"))
      (node (ref "R27") (pin "1") (pinfunction "1_1") (pintype "passive"))
      (node (ref "R30") (pin "2") (pinfunction "2_2") (pintype "passive"))
      (node (ref "U5") (pin "6") (pinfunction "-IN_6") (pintype "input"))
    )
    (net (code "47") (name "Net-(F3-Pad2)") (class "Default")
      (node (ref "F3") (pin "2") (pinfunction "2_2") (pintype "bidirectional"))
      (node (ref "X1") (pin "1") (pinfunction "1_1") (pintype "passive"))
    )
    (net (code "48") (name "Net-(LED1-PadA)") (class "Default")
      (node (ref "LED1") (pin "A") (pinfunction "A_A") (pintype "passive"))
      (node (ref "R6") (pin "1") (pinfunction "1_1") (pintype "passive"))
    )
    (net (code "49") (name "Net-(LED2-PadC)") (class "Default")
      (node (ref "LED2") (pin "C") (pinfunction "C_C") (pintype "passive"))
      (node (ref "R10") (pin "2") (pinfunction "2_2") (pintype "passive"))
    )
    (net (code "50") (name "Net-(LED3-PadA)") (class "Default")
      (node (ref "LED3") (pin "A") (pinfunction "A_A") (pintype "passive"))
      (node (ref "R5") (pin "1") (pinfunction "1_1") (pintype "passive"))
    )
    (net (code "51") (name "Net-(LED4-PadA)") (class "Default")
      (node (ref "LED4") (pin "A") (pinfunction "A_A") (pintype "passive"))
      (node (ref "R4") (pin "1") (pinfunction "1_1") (pintype "passive"))
    )
    (net (code "52") (name "Net-(Q3-B)") (class "Default")
      (node (ref "Q3") (pin "1") (pinfunction "B_1") (pintype "passive"))
      (node (ref "R9") (pin "2") (pinfunction "2_2") (pintype "passive"))
      (node (ref "ZENER1") (pin "1") (pinfunction "1_1") (pintype "passive"))
    )
    (net (code "53") (name "Net-(R7-Pad1)") (class "Default")
      (node (ref "R7") (pin "1") (pinfunction "1_1") (pintype "passive"))
      (node (ref "ZENER1") (pin "2") (pinfunction "2_2") (pintype "passive"))
    )
    (net (code "54") (name "Net-(R16-Pad2)") (class "Default")
      (node (ref "R16") (pin "2") (pinfunction "2_2") (pintype "passive"))
      (node (ref "X3") (pin "1") (pinfunction "1_1") (pintype "passive"))
    )
    (net (code "55") (name "Net-(R21-Pad2)") (class "Default")
      (node (ref "R21") (pin "2") (pinfunction "2_2") (pintype "passive"))
      (node (ref "R22") (pin "2") (pinfunction "2_2") (pintype "passive"))
      (node (ref "X4") (pin "1") (pinfunction "1_1") (pintype "passive"))
    )
    (net (code "56") (name "Net-(U$14-CHIP_EN)") (class "Default")
      (node (ref "R33") (pin "2") (pinfunction "2_2") (pintype "passive"))
      (node (ref "R34") (pin "2") (pinfunction "2_2") (pintype "passive"))
      (node (ref "U$14") (pin "J22") (pinfunction "CHIP_EN_J22") (pintype "input"))
    )
    (net (code "57") (name "Net-(U$14-GPIO_15)") (class "Default")
      (node (ref "LED1") (pin "C") (pinfunction "C_C") (pintype "passive"))
      (node (ref "U$14") (pin "J26") (pinfunction "GPIO_15_J26") (pintype "bidirectional"))
    )
    (net (code "58") (name "Net-(U$14-GPIO_16)") (class "Default")
      (node (ref "LED3") (pin "C") (pinfunction "C_C") (pintype "passive"))
      (node (ref "U$14") (pin "J27") (pinfunction "GPIO_16_J27") (pintype "bidirectional"))
    )
    (net (code "59") (name "Net-(U$14-GPIO_18)") (class "Default")
      (node (ref "LED4") (pin "C") (pinfunction "C_C") (pintype "passive"))
      (node (ref "U$14") (pin "J1") (pinfunction "GPIO_18_J1") (pintype "bidirectional"))
    )
    (net (code "60") (name "Net-(U$14-SPI_CFG)") (class "Default")
      (node (ref "R35") (pin "2") (pinfunction "2_2") (pintype "passive"))
      (node (ref "U$14") (pin "J10") (pinfunction "SPI_CFG_J10") (pintype "input"))
    )
    (net (code "61") (name "Net-(U$14-WAKE)") (class "Default")
      (node (ref "R3") (pin "1") (pinfunction "1_1") (pintype "passive"))
      (node (ref "U$14") (pin "J11") (pinfunction "WAKE_J11") (pintype "input"))
    )
    (net (code "62") (name "Net-(U3-AREF)") (class "Default")
      (node (ref "C21") (pin "2") (pinfunction "2_2") (pintype "passive"))
      (node (ref "U3") (pin "98") (pinfunction "AREF_98") (pintype "bidirectional"))
    )
    (net (code "63") (name "Net-(U3-XTAL1)") (class "Default")
      (node (ref "C20") (pin "2") (pinfunction "2_2") (pintype "passive"))
      (node (ref "Q4") (pin "1") (pinfunction "1_1") (pintype "passive"))
      (node (ref "R12") (pin "1") (pinfunction "1_1") (pintype "passive"))
      (node (ref "U3") (pin "34") (pinfunction "XTAL1_34") (pintype "input"))
    )
    (net (code "64") (name "Net-(U3-XTAL2)") (class "Default")
      (node (ref "C19") (pin "2") (pinfunction "2_2") (pintype "passive"))
      (node (ref "Q4") (pin "2") (pinfunction "2_2") (pintype "passive"))
      (node (ref "R12") (pin "2") (pinfunction "2_2") (pintype "passive"))
      (node (ref "U3") (pin "33") (pinfunction "XTAL2_33") (pintype "output"))
    )
    (net (code "65") (name "Net-(U4-ADDR)") (class "Default")
      (node (ref "R32") (pin "2") (pinfunction "2_2") (pintype "passive"))
      (node (ref "U4") (pin "1") (pinfunction "ADDR_1") (pintype "input"))
    )
    (net (code "66") (name "Net-(U4-ALERT{slash}RDY)") (class "Default")
      (node (ref "R31") (pin "2") (pinfunction "2_2") (pintype "passive"))
      (node (ref "U4") (pin "2") (pinfunction "ALERT/RDY_2") (pintype "input"))
    )
    (net (code "67") (name "Net-(VR2-FEEDBACK)") (class "Default")
      (node (ref "C14") (pin "+") (pinfunction "+_+") (pintype "passive"))
      (node (ref "C16") (pin "1") (pinfunction "1_1") (pintype "passive"))
      (node (ref "F2") (pin "1") (pinfunction "1_1") (pintype "bidirectional"))
      (node (ref "L2") (pin "1") (pinfunction "1_1") (pintype "passive"))
      (node (ref "VR2") (pin "4") (pinfunction "FEEDBACK_4") (pintype "input"))
    )
    (net (code "68") (name "Net-(VR2-OUTPUT)") (class "Default")
      (node (ref "D5") (pin "C") (pinfunction "C_C") (pintype "passive"))
      (node (ref "L2") (pin "2") (pinfunction "2_2") (pintype "passive"))
      (node (ref "VR2") (pin "2") (pinfunction "OUTPUT_2") (pintype "output"))
    )
    (net (code "69") (name "Net-(X1B-1)") (class "Default")
      (node (ref "F1") (pin "2") (pinfunction "2_2") (pintype "bidirectional"))
      (node (ref "X1") (pin "2") (pinfunction "1_2") (pintype "passive"))
    )
    (net (code "70") (name "Net-(X2B-1)") (class "Default")
      (node (ref "D4") (pin "2") (pinfunction "2_2") (pintype "bidirectional"))
      (node (ref "D6") (pin "A") (pinfunction "A_A") (pintype "passive"))
      (node (ref "X2") (pin "1") (pinfunction "1_1") (pintype "passive"))
      (node (ref "X2") (pin "2") (pinfunction "1_2") (pintype "passive"))
    )
    (net (code "71") (name "Net-(X3B-1)") (class "Default")
      (node (ref "R15") (pin "2") (pinfunction "2_2") (pintype "passive"))
      (node (ref "X3") (pin "2") (pinfunction "1_2") (pintype "passive"))
    )
    (net (code "72") (name "Net-(X3C-1)") (class "Default")
      (node (ref "R14") (pin "2") (pinfunction "2_2") (pintype "passive"))
      (node (ref "X3") (pin "3") (pinfunction "1_3") (pintype "passive"))
    )
    (net (code "73") (name "Net-(X3D-1)") (class "Default")
      (node (ref "R13") (pin "2") (pinfunction "2_2") (pintype "passive"))
      (node (ref "X3") (pin "4") (pinfunction "1_4") (pintype "passive"))
    )
    (net (code "74") (name "Net-(X4B-1)") (class "Default")
      (node (ref "D11") (pin "A") (pinfunction "A_A") (pintype "passive"))
      (node (ref "X4") (pin "2") (pinfunction "1_2") (pintype "passive"))
    )
    (net (code "75") (name "Net-(X4C-1)") (class "Default")
      (node (ref "R26") (pin "2") (pinfunction "2_2") (pintype "passive"))
      (node (ref "R27") (pin "2") (pinfunction "2_2") (pintype "passive"))
      (node (ref "X4") (pin "3") (pinfunction "1_3") (pintype "passive"))
    )
    (net (code "76") (name "Net-(X4D-1)") (class "Default")
      (node (ref "D12") (pin "A") (pinfunction "A_A") (pintype "passive"))
      (node (ref "X4") (pin "4") (pinfunction "1_4") (pintype "passive"))
    )
    (net (code "77") (name "VCCA") (class "Default")
      (node (ref "C27") (pin "1") (pinfunction "1_1") (pintype "passive"))
      (node (ref "D13") (pin "1") (pinfunction "K_1") (pintype "bidirectional"))
      (node (ref "D14") (pin "1") (pinfunction "K_1") (pintype "bidirectional"))
      (node (ref "D15") (pin "1") (pinfunction "K_1") (pintype "bidirectional"))
      (node (ref "D16") (pin "1") (pinfunction "K_1") (pintype "bidirectional"))
      (node (ref "FB1") (pin "2") (pinfunction "2_2") (pintype "passive"))
      (node (ref "R31") (pin "1") (pinfunction "1_1") (pintype "passive"))
      (node (ref "U4") (pin "8") (pinfunction "VDD_8") (pintype "power_in"))
      (node (ref "U5") (pin "8") (pinfunction "P$V+_8") (pintype "bidirectional"))
    )
    (net (code "78") (name "unconnected-(SD1-DAT1-Pad8)") (class "Default")
      (node (ref "SD1") (pin "8") (pinfunction "DAT1_8") (pintype "bidirectional"))
    )
    (net (code "79") (name "unconnected-(SD1-DAT2-Pad1)") (class "Default")
      (node (ref "SD1") (pin "1") (pinfunction "DAT2_1") (pintype "bidirectional"))
    )
    (net (code "80") (name "unconnected-(U$14-1P3V_TP-PadJ24)") (class "Default")
      (node (ref "U$14") (pin "J24") (pinfunction "1P3V_TP_J24") (pintype "passive"))
    )
    (net (code "81") (name "unconnected-(U$14-GPIO_1-PadJ21)") (class "Default")
      (node (ref "U$14") (pin "J21") (pinfunction "GPIO_1_J21") (pintype "bidirectional"))
    )
    (net (code "82") (name "unconnected-(U$14-I2C_SCL-PadJ2)") (class "Default")
      (node (ref "U$14") (pin "J2") (pinfunction "I2C_SCL_J2") (pintype "bidirectional"))
    )
    (net (code "83") (name "unconnected-(U$14-I2C_SDA-PadJ3)") (class "Default")
      (node (ref "U$14") (pin "J3") (pinfunction "I2C_SDA_J3") (pintype "bidirectional"))
    )
    (net (code "84") (name "unconnected-(U$14-UART_RXD-PadJ19)") (class "Default")
      (node (ref "U$14") (pin "J19") (pinfunction "UART_RXD_J19") (pintype "input"))
    )
    (net (code "85") (name "unconnected-(U$14-UART_TXD-PadJ14)") (class "Default")
      (node (ref "U$14") (pin "J14") (pinfunction "UART_TXD_J14") (pintype "output"))
    )
    (net (code "86") (name "unconnected-(U1-A8-Pad9)") (class "Default")
      (node (ref "U1") (pin "9") (pinfunction "A8_9") (pintype "bidirectional"))
    )
    (net (code "87") (name "unconnected-(U1-B8-Pad11)") (class "Default")
      (node (ref "U1") (pin "11") (pinfunction "B8_11") (pintype "bidirectional"))
    )
    (net (code "88") (name "unconnected-(U3-(A8)PC0-Pad53)") (class "Default")
      (node (ref "U3") (pin "53") (pinfunction "(A8)PC0_53") (pintype "bidirectional"))
    )
    (net (code "89") (name "unconnected-(U3-(A9)PC1-Pad54)") (class "Default")
      (node (ref "U3") (pin "54") (pinfunction "(A9)PC1_54") (pintype "bidirectional"))
    )
    (net (code "90") (name "unconnected-(U3-(A10)PC2-Pad55)") (class "Default")
      (node (ref "U3") (pin "55") (pinfunction "(A10)PC2_55") (pintype "bidirectional"))
    )
    (net (code "91") (name "unconnected-(U3-(A11)PC3-Pad56)") (class "Default")
      (node (ref "U3") (pin "56") (pinfunction "(A11)PC3_56") (pintype "bidirectional"))
    )
    (net (code "92") (name "unconnected-(U3-(A12)PC4-Pad57)") (class "Default")
      (node (ref "U3") (pin "57") (pinfunction "(A12)PC4_57") (pintype "bidirectional"))
    )
    (net (code "93") (name "unconnected-(U3-(A13)PC5-Pad58)") (class "Default")
      (node (ref "U3") (pin "58") (pinfunction "(A13)PC5_58") (pintype "bidirectional"))
    )
    (net (code "94") (name "unconnected-(U3-(A14)PC6-Pad59)") (class "Default")
      (node (ref "U3") (pin "59") (pinfunction "(A14)PC6_59") (pintype "bidirectional"))
    )
    (net (code "95") (name "unconnected-(U3-(A15)PC7-Pad60)") (class "Default")
      (node (ref "U3") (pin "60") (pinfunction "(A15)PC7_60") (pintype "bidirectional"))
    )
    (net (code "96") (name "unconnected-(U3-(AD0)PA0-Pad78)") (class "Default")
      (node (ref "U3") (pin "78") (pinfunction "(AD0)PA0_78") (pintype "bidirectional"))
    )
    (net (code "97") (name "unconnected-(U3-(AD1)PA1-Pad77)") (class "Default")
      (node (ref "U3") (pin "77") (pinfunction "(AD1)PA1_77") (pintype "bidirectional"))
    )
    (net (code "98") (name "unconnected-(U3-(AD3)PA3-Pad75)") (class "Default")
      (node (ref "U3") (pin "75") (pinfunction "(AD3)PA3_75") (pintype "bidirectional"))
    )
    (net (code "99") (name "unconnected-(U3-(AD4)PA4-Pad74)") (class "Default")
      (node (ref "U3") (pin "74") (pinfunction "(AD4)PA4_74") (pintype "bidirectional"))
    )
    (net (code "100") (name "unconnected-(U3-(AD5)PA5-Pad73)") (class "Default")
      (node (ref "U3") (pin "73") (pinfunction "(AD5)PA5_73") (pintype "bidirectional"))
    )
    (net (code "101") (name "unconnected-(U3-(AD6)PA6-Pad72)") (class "Default")
      (node (ref "U3") (pin "72") (pinfunction "(AD6)PA6_72") (pintype "bidirectional"))
    )
    (net (code "102") (name "unconnected-(U3-(AD7)PA7-Pad71)") (class "Default")
      (node (ref "U3") (pin "71") (pinfunction "(AD7)PA7_71") (pintype "bidirectional"))
    )
    (net (code "103") (name "unconnected-(U3-(ADC0)PF0-Pad97)") (class "Default")
      (node (ref "U3") (pin "97") (pinfunction "(ADC0)PF0_97") (pintype "bidirectional"))
    )
    (net (code "104") (name "unconnected-(U3-(ADC1)PF1-Pad96)") (class "Default")
      (node (ref "U3") (pin "96") (pinfunction "(ADC1)PF1_96") (pintype "bidirectional"))
    )
    (net (code "105") (name "unconnected-(U3-(ADC2)PF2-Pad95)") (class "Default")
      (node (ref "U3") (pin "95") (pinfunction "(ADC2)PF2_95") (pintype "bidirectional"))
    )
    (net (code "106") (name "unconnected-(U3-(ADC3)PF3-Pad94)") (class "Default")
      (node (ref "U3") (pin "94") (pinfunction "(ADC3)PF3_94") (pintype "bidirectional"))
    )
    (net (code "107") (name "unconnected-(U3-(ADC4{slash}TCK)PF4-Pad93)") (class "Default")
      (node (ref "U3") (pin "93") (pinfunction "(ADC4/TCK)PF4_93") (pintype "bidirectional"))
    )
    (net (code "108") (name "unconnected-(U3-(ADC5{slash}TMS)PF5-Pad92)") (class "Default")
      (node (ref "U3") (pin "92") (pinfunction "(ADC5/TMS)PF5_92") (pintype "bidirectional"))
    )
    (net (code "109") (name "unconnected-(U3-(ADC6{slash}TDO)PF6-Pad91)") (class "Default")
      (node (ref "U3") (pin "91") (pinfunction "(ADC6/TDO)PF6_91") (pintype "bidirectional"))
    )
    (net (code "110") (name "unconnected-(U3-(ADC7{slash}TDI)PF7-Pad90)") (class "Default")
      (node (ref "U3") (pin "90") (pinfunction "(ADC7/TDI)PF7_90") (pintype "bidirectional"))
    )
    (net (code "111") (name "unconnected-(U3-(ALE)PG2-Pad70)") (class "Default")
      (node (ref "U3") (pin "70") (pinfunction "(ALE)PG2_70") (pintype "bidirectional"))
    )
    (net (code "112") (name "unconnected-(U3-(CLKO{slash}ICP3{slash}INT7)PE7-Pad9)") (class "Default")
      (node (ref "U3") (pin "9") (pinfunction "(CLKO/ICP3/INT7)PE7_9") (pintype "bidirectional"))
    )
    (net (code "113") (name "unconnected-(U3-(ICP1)PD4-Pad47)") (class "Default")
      (node (ref "U3") (pin "47") (pinfunction "(ICP1)PD4_47") (pintype "bidirectional"))
    )
    (net (code "114") (name "unconnected-(U3-(OC0A{slash}OC1C{slash}PCINT7)PB7-Pad26)") (class "Default")
      (node (ref "U3") (pin "26") (pinfunction "(OC0A/OC1C/PCINT7)PB7_26") (pintype "bidirectional"))
    )
    (net (code "115") (name "unconnected-(U3-(OC1B{slash}PCINT6)PB6-Pad25)") (class "Default")
      (node (ref "U3") (pin "25") (pinfunction "(OC1B/PCINT6)PB6_25") (pintype "bidirectional"))
    )
    (net (code "116") (name "unconnected-(U3-(OC3A{slash}AIN1)PE3-Pad5)") (class "Default")
      (node (ref "U3") (pin "5") (pinfunction "(OC3A/AIN1)PE3_5") (pintype "bidirectional"))
    )
    (net (code "117") (name "unconnected-(U3-(OC3C{slash}INT5)PE5-Pad7)") (class "Default")
      (node (ref "U3") (pin "7") (pinfunction "(OC3C/INT5)PE5_7") (pintype "bidirectional"))
    )
    (net (code "118") (name "unconnected-(U3-(RD)PG1-Pad52)") (class "Default")
      (node (ref "U3") (pin "52") (pinfunction "(RD)PG1_52") (pintype "bidirectional"))
    )
    (net (code "119") (name "unconnected-(U3-(RXD1{slash}INT2)PD2-Pad45)") (class "Default")
      (node (ref "U3") (pin "45") (pinfunction "(RXD1/INT2)PD2_45") (pintype "bidirectional"))
    )
    (net (code "120") (name "unconnected-(U3-(T0)PD7-Pad50)") (class "Default")
      (node (ref "U3") (pin "50") (pinfunction "(T0)PD7_50") (pintype "bidirectional"))
    )
    (net (code "121") (name "unconnected-(U3-(T1)PD6-Pad49)") (class "Default")
      (node (ref "U3") (pin "49") (pinfunction "(T1)PD6_49") (pintype "bidirectional"))
    )
    (net (code "122") (name "unconnected-(U3-(T3{slash}INT6)PE6-Pad8)") (class "Default")
      (node (ref "U3") (pin "8") (pinfunction "(T3/INT6)PE6_8") (pintype "bidirectional"))
    )
    (net (code "123") (name "unconnected-(U3-(TOSC1)PG4-Pad29)") (class "Default")
      (node (ref "U3") (pin "29") (pinfunction "(TOSC1)PG4_29") (pintype "bidirectional"))
    )
    (net (code "124") (name "unconnected-(U3-(TOSC2)PG3-Pad28)") (class "Default")
      (node (ref "U3") (pin "28") (pinfunction "(TOSC2)PG3_28") (pintype "bidirectional"))
    )
    (net (code "125") (name "unconnected-(U3-(TXD1{slash}INT3)PD3-Pad46)") (class "Default")
      (node (ref "U3") (pin "46") (pinfunction "(TXD1/INT3)PD3_46") (pintype "bidirectional"))
    )
    (net (code "126") (name "unconnected-(U3-(WR)PG0-Pad51)") (class "Default")
      (node (ref "U3") (pin "51") (pinfunction "(WR)PG0_51") (pintype "bidirectional"))
    )
    (net (code "127") (name "unconnected-(U3-(XCK0{slash}AIN0)PE2-Pad4)") (class "Default")
      (node (ref "U3") (pin "4") (pinfunction "(XCK0/AIN0)PE2_4") (pintype "bidirectional"))
    )
    (net (code "128") (name "unconnected-(U3-(XCK1)PD5-Pad48)") (class "Default")
      (node (ref "U3") (pin "48") (pinfunction "(XCK1)PD5_48") (pintype "bidirectional"))
    )
    (net (code "129") (name "unconnected-(U3-PH0(RXD2)-Pad12)") (class "Default")
      (node (ref "U3") (pin "12") (pinfunction "PH0(RXD2)_12") (pintype "bidirectional"))
    )
    (net (code "130") (name "unconnected-(U3-PH1(TXD2)-Pad13)") (class "Default")
      (node (ref "U3") (pin "13") (pinfunction "PH1(TXD2)_13") (pintype "bidirectional"))
    )
    (net (code "131") (name "unconnected-(U3-PH2(XCK2)-Pad14)") (class "Default")
      (node (ref "U3") (pin "14") (pinfunction "PH2(XCK2)_14") (pintype "bidirectional"))
    )
    (net (code "132") (name "unconnected-(U3-PH3(OC4A)-Pad15)") (class "Default")
      (node (ref "U3") (pin "15") (pinfunction "PH3(OC4A)_15") (pintype "bidirectional"))
    )
    (net (code "133") (name "unconnected-(U3-PH4(OC4B)-Pad16)") (class "Default")
      (node (ref "U3") (pin "16") (pinfunction "PH4(OC4B)_16") (pintype "bidirectional"))
    )
    (net (code "134") (name "unconnected-(U3-PH7(T4)-Pad27)") (class "Default")
      (node (ref "U3") (pin "27") (pinfunction "PH7(T4)_27") (pintype "bidirectional"))
    )
    (net (code "135") (name "unconnected-(U3-PJ2(XCK3{slash}PCINT11)-Pad65)") (class "Default")
      (node (ref "U3") (pin "65") (pinfunction "PJ2(XCK3/PCINT11)_65") (pintype "bidirectional"))
    )
    (net (code "136") (name "unconnected-(U3-PJ3(PCINT12)-Pad66)") (class "Default")
      (node (ref "U3") (pin "66") (pinfunction "PJ3(PCINT12)_66") (pintype "bidirectional"))
    )
    (net (code "137") (name "unconnected-(U3-PJ4(PCINT13)-Pad67)") (class "Default")
      (node (ref "U3") (pin "67") (pinfunction "PJ4(PCINT13)_67") (pintype "bidirectional"))
    )
    (net (code "138") (name "unconnected-(U3-PJ5(PCINT14)-Pad68)") (class "Default")
      (node (ref "U3") (pin "68") (pinfunction "PJ5(PCINT14)_68") (pintype "bidirectional"))
    )
    (net (code "139") (name "unconnected-(U3-PJ6(PCINT15)-Pad69)") (class "Default")
      (node (ref "U3") (pin "69") (pinfunction "PJ6(PCINT15)_69") (pintype "bidirectional"))
    )
    (net (code "140") (name "unconnected-(U3-PJ7-Pad79)") (class "Default")
      (node (ref "U3") (pin "79") (pinfunction "PJ7_79") (pintype "bidirectional"))
    )
    (net (code "141") (name "unconnected-(U3-PK0(ADC8{slash}PCINT16)-Pad89)") (class "Default")
      (node (ref "U3") (pin "89") (pinfunction "PK0(ADC8/PCINT16)_89") (pintype "bidirectional"))
    )
    (net (code "142") (name "unconnected-(U3-PK1(ADC9{slash}PCINT17)-Pad88)") (class "Default")
      (node (ref "U3") (pin "88") (pinfunction "PK1(ADC9/PCINT17)_88") (pintype "bidirectional"))
    )
    (net (code "143") (name "unconnected-(U3-PK2(ADC10{slash}PCINT18)-Pad87)") (class "Default")
      (node (ref "U3") (pin "87") (pinfunction "PK2(ADC10/PCINT18)_87") (pintype "bidirectional"))
    )
    (net (code "144") (name "unconnected-(U3-PK3(ADC11{slash}PCINT19)-Pad86)") (class "Default")
      (node (ref "U3") (pin "86") (pinfunction "PK3(ADC11/PCINT19)_86") (pintype "bidirectional"))
    )
    (net (code "145") (name "unconnected-(U3-PL0(ICP4)-Pad35)") (class "Default")
      (node (ref "U3") (pin "35") (pinfunction "PL0(ICP4)_35") (pintype "bidirectional"))
    )
    (net (code "146") (name "unconnected-(U3-PL1(ICP5)-Pad36)") (class "Default")
      (node (ref "U3") (pin "36") (pinfunction "PL1(ICP5)_36") (pintype "bidirectional"))
    )
    (net (code "147") (name "unconnected-(U3-PL2(T5)-Pad37)") (class "Default")
      (node (ref "U3") (pin "37") (pinfunction "PL2(T5)_37") (pintype "bidirectional"))
    )
    (net (code "148") (name "unconnected-(U3-PL3(OC5A)-Pad38)") (class "Default")
      (node (ref "U3") (pin "38") (pinfunction "PL3(OC5A)_38") (pintype "bidirectional"))
    )
    (net (code "149") (name "unconnected-(U3-PL4(OC5B)-Pad39)") (class "Default")
      (node (ref "U3") (pin "39") (pinfunction "PL4(OC5B)_39") (pintype "bidirectional"))
    )
    (net (code "150") (name "unconnected-(U3-PL5(OC5C)-Pad40)") (class "Default")
      (node (ref "U3") (pin "40") (pinfunction "PL5(OC5C)_40") (pintype "bidirectional"))
    )
    (net (code "151") (name "unconnected-(U3-PL6-Pad41)") (class "Default")
      (node (ref "U3") (pin "41") (pinfunction "PL6_41") (pintype "bidirectional"))
    )
    (net (code "152") (name "unconnected-(U3-PL7-Pad42)") (class "Default")
      (node (ref "U3") (pin "42") (pinfunction "PL7_42") (pintype "bidirectional"))
    )
    (net (code "153") (name "unconnected-(U4-AIN2-Pad6)") (class "Default")
      (node (ref "U4") (pin "6") (pinfunction "AIN2_6") (pintype "input"))
    )
    (net (code "154") (name "unconnected-(U4-AIN3-Pad7)") (class "Default")
      (node (ref "U4") (pin "7") (pinfunction "AIN3_7") (pintype "input"))
    )
  )
)
